# Magnetometer_v2.net
KiCad netlist of a schematic drawn in EAGLE
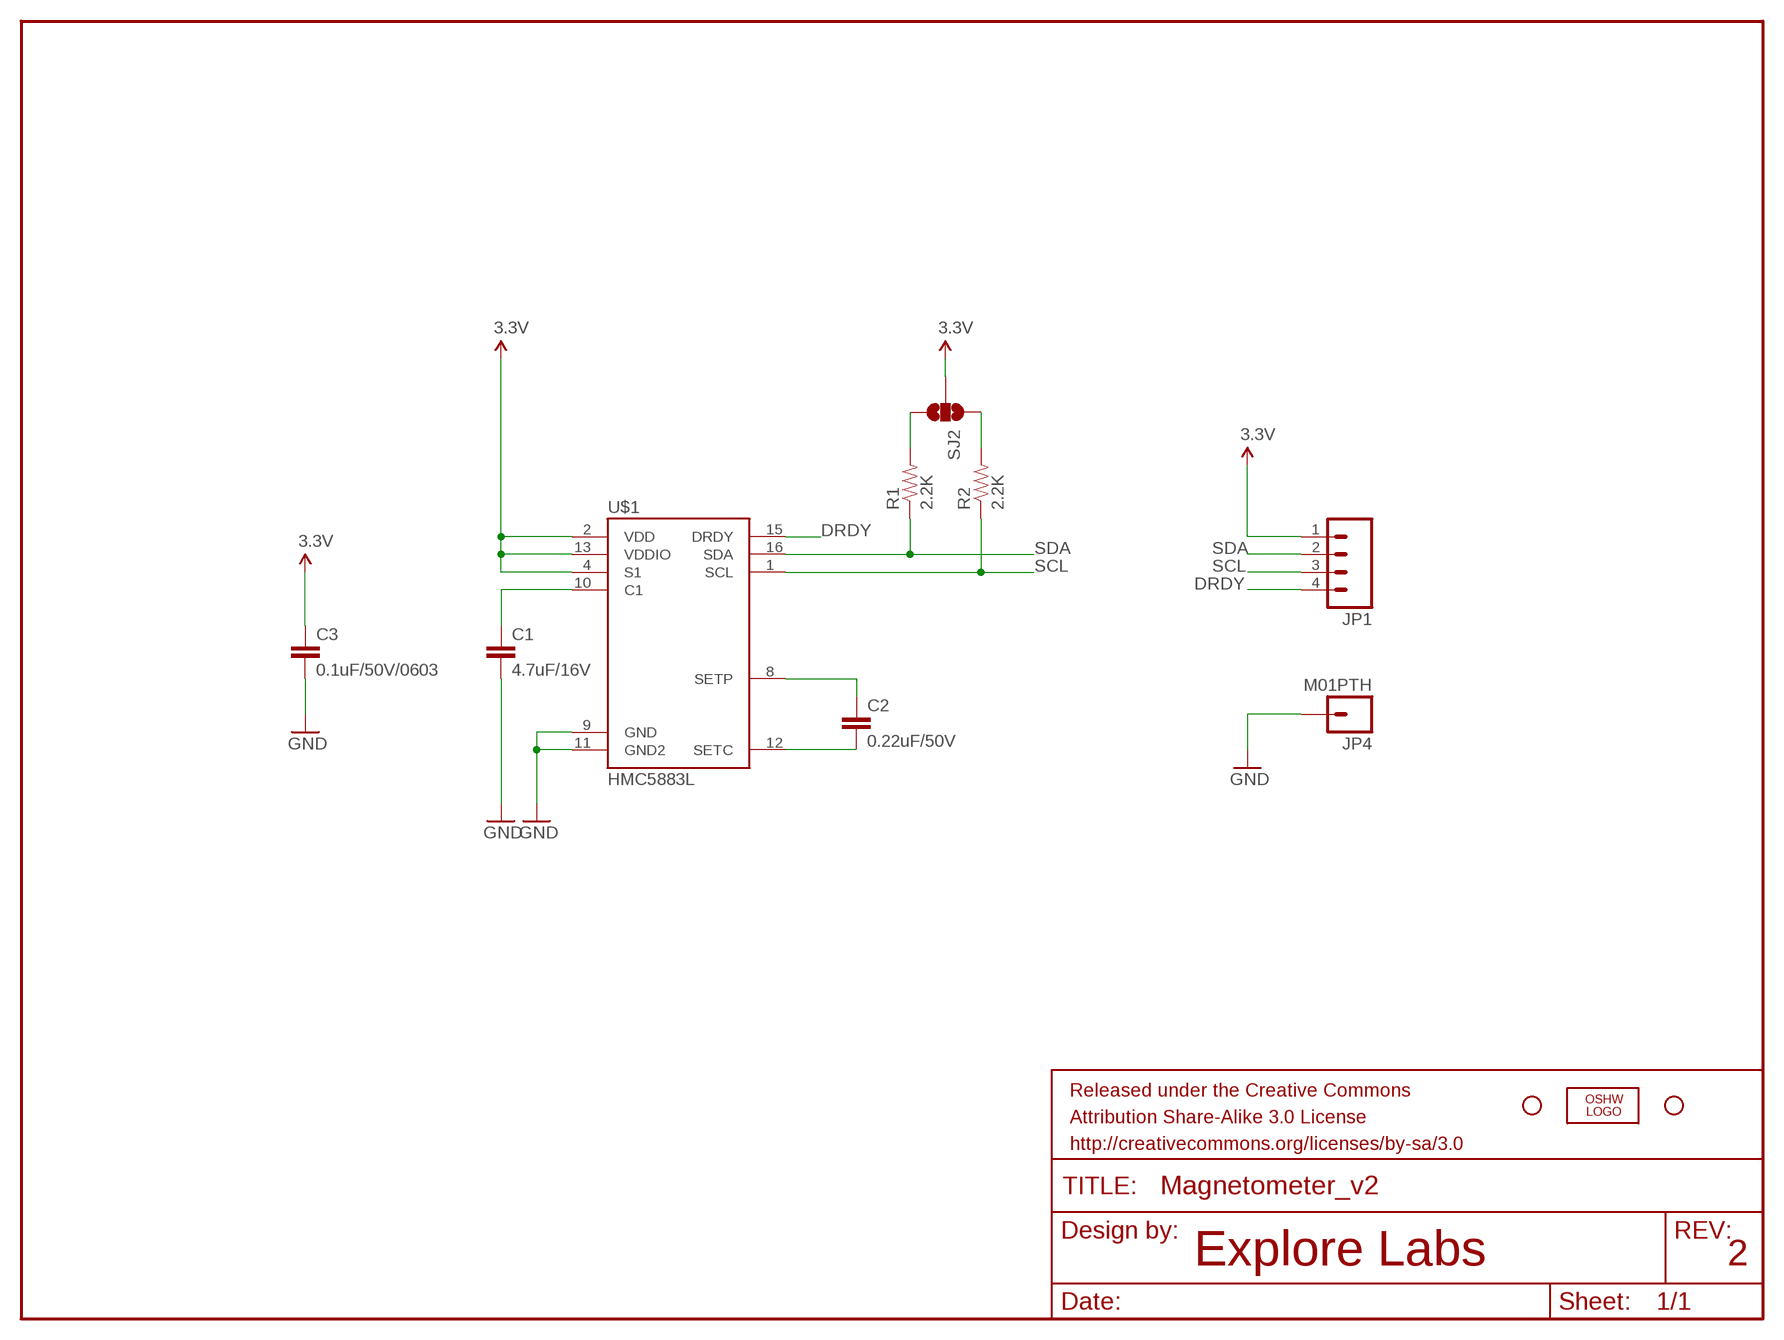
[diagram p0: schematic, sheet 1]

(export (version "E")
  (design (tool "Eeschema 10.0.6"))
  (components
    (comp (ref "C1")
      (value "4.7uF/16V")
      (footprint "eagle-import:1206")
      (libsource (lib "eagle-import") (part "CAP1206"))
    )
    (comp (ref "C2")
      (value "0.22uF/50V")
      (footprint "eagle-import:1206")
      (libsource (lib "eagle-import") (part "CAP1206"))
    )
    (comp (ref "C3")
      (value "0.1uF/50V/0603")
      (footprint "eagle-import:0603-CAP")
      (libsource (lib "eagle-import") (part "CAP0603-CAP"))
    )
    (comp (ref "JP1")
      (value "M04PTH")
      (footprint "eagle-import:1X04")
      (libsource (lib "eagle-import") (part "M04PTH"))
    )
    (comp (ref "JP2")
      (value "STAND-OFFTIGHT")
      (footprint "eagle-import:STAND-OFF-TIGHT")
      (libsource (lib "eagle-import") (part "STAND-OFFTIGHT"))
    )
    (comp (ref "JP3")
      (value "STAND-OFFTIGHT")
      (footprint "eagle-import:STAND-OFF-TIGHT")
      (libsource (lib "eagle-import") (part "STAND-OFFTIGHT"))
    )
    (comp (ref "JP4")
      (value "M01PTH")
      (footprint "eagle-import:1X01")
      (libsource (lib "eagle-import") (part "M01PTH"))
    )
    (comp (ref "LOGO1")
      (value "OSHW_LOGO_FILLX0150-NT")
      (footprint "eagle-import:OSHW_FILLX150_NOTEXT")
      (libsource (lib "eagle-import") (part "OSHW_LOGO_FILLX0150-NT"))
    )
    (comp (ref "R1")
      (value "2.2K")
      (footprint "eagle-import:0603-RES")
      (libsource (lib "eagle-import") (part "RESISTOR0603-RES"))
    )
    (comp (ref "R2")
      (value "2.2K")
      (footprint "eagle-import:0603-RES")
      (libsource (lib "eagle-import") (part "RESISTOR0603-RES"))
    )
    (comp (ref "SJ2")
      (value "SOLDERJUMPER_2WAYS")
      (footprint "eagle-import:SJ_3")
      (libsource (lib "eagle-import") (part "SOLDERJUMPER_2WAYS"))
    )
    (comp (ref "U$1")
      (value "HMC5883L")
      (footprint "eagle-import:LPCC16")
      (libsource (lib "eagle-import") (part "HMC5883L"))
    )
  )
  (nets
    (net (code "1") (name "/DRDY") (class "Default")
      (node (ref "JP1") (pin "4") (pinfunction "4_4") (pintype "passive"))
      (node (ref "U$1") (pin "15") (pinfunction "DRDY_15") (pintype "bidirectional"))
    )
    (net (code "2") (name "/SCL") (class "Default")
      (node (ref "JP1") (pin "3") (pinfunction "3_3") (pintype "passive"))
      (node (ref "R2") (pin "1") (pinfunction "1_1") (pintype "passive"))
      (node (ref "U$1") (pin "1") (pinfunction "SCL_1") (pintype "bidirectional"))
    )
    (net (code "3") (name "/SDA") (class "Default")
      (node (ref "JP1") (pin "2") (pinfunction "2_2") (pintype "passive"))
      (node (ref "R1") (pin "1") (pinfunction "1_1") (pintype "passive"))
      (node (ref "U$1") (pin "16") (pinfunction "SDA_16") (pintype "bidirectional"))
    )
    (net (code "4") (name "3.3V") (class "Default")
      (node (ref "C3") (pin "1") (pinfunction "1_1") (pintype "passive"))
      (node (ref "JP1") (pin "1") (pinfunction "1_1") (pintype "passive"))
      (node (ref "SJ2") (pin "2") (pinfunction "2_2") (pintype "passive"))
      (node (ref "U$1") (pin "13") (pinfunction "VDDIO_13") (pintype "bidirectional"))
      (node (ref "U$1") (pin "2") (pinfunction "VDD_2") (pintype "bidirectional"))
      (node (ref "U$1") (pin "4") (pinfunction "S1_4") (pintype "bidirectional"))
    )
    (net (code "5") (name "GND") (class "Default")
      (node (ref "C1") (pin "2") (pinfunction "2_2") (pintype "passive"))
      (node (ref "C3") (pin "2") (pinfunction "2_2") (pintype "passive"))
      (node (ref "JP4") (pin "1") (pinfunction "1_1") (pintype "passive"))
      (node (ref "U$1") (pin "11") (pinfunction "GND2_11") (pintype "bidirectional"))
      (node (ref "U$1") (pin "9") (pinfunction "GND_9") (pintype "bidirectional"))
    )
    (net (code "6") (name "Net-(R1-Pad2)") (class "Default")
      (node (ref "R1") (pin "2") (pinfunction "2_2") (pintype "passive"))
      (node (ref "SJ2") (pin "3") (pinfunction "3_3") (pintype "passive"))
    )
    (net (code "7") (name "Net-(R2-Pad2)") (class "Default")
      (node (ref "R2") (pin "2") (pinfunction "2_2") (pintype "passive"))
      (node (ref "SJ2") (pin "1") (pinfunction "1_1") (pintype "passive"))
    )
    (net (code "8") (name "Net-(U$1-C1)") (class "Default")
      (node (ref "C1") (pin "1") (pinfunction "1_1") (pintype "passive"))
      (node (ref "U$1") (pin "10") (pinfunction "C1_10") (pintype "bidirectional"))
    )
    (net (code "9") (name "Net-(U$1-SETC)") (class "Default")
      (node (ref "C2") (pin "2") (pinfunction "2_2") (pintype "passive"))
      (node (ref "U$1") (pin "12") (pinfunction "SETC_12") (pintype "bidirectional"))
    )
    (net (code "10") (name "Net-(U$1-SETP)") (class "Default")
      (node (ref "C2") (pin "1") (pinfunction "1_1") (pintype "passive"))
      (node (ref "U$1") (pin "8") (pinfunction "SETP_8") (pintype "bidirectional"))
    )
  )
)
